# SNES_RGBAmp.net
KiCad netlist of a schematic drawn in EAGLE
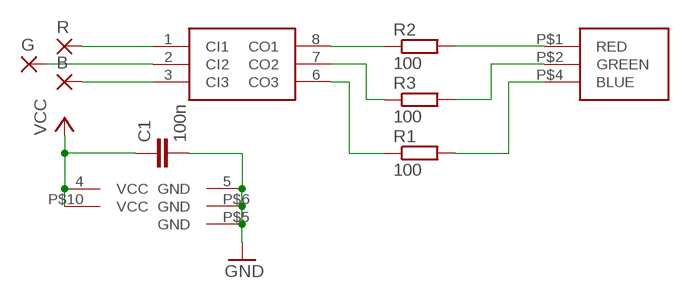
[diagram p0: schematic, sheet 1]

(export (version "E")
  (design (tool "Eeschema 10.0.6"))
  (components
    (comp (ref "B")
      (value "SMD2")
      (footprint "eagle-import:SMD1,27-2,54")
      (libsource (lib "eagle-import") (part "SMD2"))
    )
    (comp (ref "C1")
      (value "100n")
      (footprint "eagle-import:Z0805")
      (libsource (lib "eagle-import") (part "C0805"))
    )
    (comp (ref "G")
      (value "SMD2")
      (footprint "eagle-import:SMD1,27-2,54")
      (libsource (lib "eagle-import") (part "SMD2"))
    )
    (comp (ref "R")
      (value "SMD2")
      (footprint "eagle-import:SMD1,27-2,54")
      (libsource (lib "eagle-import") (part "SMD2"))
    )
    (comp (ref "R1")
      (value "100")
      (footprint "eagle-import:Z0805")
      (libsource (lib "eagle-import") (part "R0805"))
    )
    (comp (ref "R2")
      (value "100")
      (footprint "eagle-import:Z0805")
      (libsource (lib "eagle-import") (part "R0805"))
    )
    (comp (ref "R3")
      (value "100")
      (footprint "eagle-import:Z0805")
      (libsource (lib "eagle-import") (part "R0805"))
    )
    (comp (ref "U$1")
      (value "THS7314")
      (footprint "eagle-import:THS7314")
      (libsource (lib "eagle-import") (part "THS7314"))
    )
    (comp (ref "U$3")
      (value "SNES_MULTIAV_RGB_ONLY")
      (footprint "eagle-import:SNES_MULTIAV_RGB_ONLY")
      (libsource (lib "eagle-import") (part "SNES_MULTIAV_RGB_ONLY"))
    )
  )
  (nets
    (net (code "1") (name "GND") (class "Default")
      (node (ref "C1") (pin "2") (pinfunction "2_2") (pintype "passive"))
      (node (ref "U$1") (pin "5") (pinfunction "GND_5") (pintype "bidirectional"))
      (node (ref "U$3") (pin "P$5") (pinfunction "GND_P$5") (pintype "bidirectional"))
      (node (ref "U$3") (pin "P$6") (pinfunction "GND_P$6") (pintype "bidirectional"))
    )
    (net (code "2") (name "Net-(B-P)") (class "Default")
      (node (ref "B") (pin "1") (pinfunction "P_1") (pintype "passive"))
      (node (ref "U$1") (pin "3") (pinfunction "CI3_3") (pintype "bidirectional"))
    )
    (net (code "3") (name "Net-(G-P)") (class "Default")
      (node (ref "G") (pin "1") (pinfunction "P_1") (pintype "passive"))
      (node (ref "U$1") (pin "2") (pinfunction "CI2_2") (pintype "bidirectional"))
    )
    (net (code "4") (name "Net-(R-P)") (class "Default")
      (node (ref "R") (pin "1") (pinfunction "P_1") (pintype "passive"))
      (node (ref "U$1") (pin "1") (pinfunction "CI1_1") (pintype "bidirectional"))
    )
    (net (code "5") (name "Net-(U$1A-CO1)") (class "Default")
      (node (ref "R2") (pin "1") (pinfunction "1_1") (pintype "passive"))
      (node (ref "U$1") (pin "8") (pinfunction "CO1_8") (pintype "bidirectional"))
    )
    (net (code "6") (name "Net-(U$1A-CO2)") (class "Default")
      (node (ref "R3") (pin "1") (pinfunction "1_1") (pintype "passive"))
      (node (ref "U$1") (pin "7") (pinfunction "CO2_7") (pintype "bidirectional"))
    )
    (net (code "7") (name "Net-(U$1A-CO3)") (class "Default")
      (node (ref "R1") (pin "1") (pinfunction "1_1") (pintype "passive"))
      (node (ref "U$1") (pin "6") (pinfunction "CO3_6") (pintype "bidirectional"))
    )
    (net (code "8") (name "Net-(U$3C-BLUE)") (class "Default")
      (node (ref "R1") (pin "2") (pinfunction "2_2") (pintype "passive"))
      (node (ref "U$3") (pin "P$4") (pinfunction "BLUE_P$4") (pintype "bidirectional"))
    )
    (net (code "9") (name "Net-(U$3C-GREEN)") (class "Default")
      (node (ref "R3") (pin "2") (pinfunction "2_2") (pintype "passive"))
      (node (ref "U$3") (pin "P$2") (pinfunction "GREEN_P$2") (pintype "bidirectional"))
    )
    (net (code "10") (name "Net-(U$3C-RED)") (class "Default")
      (node (ref "R2") (pin "2") (pinfunction "2_2") (pintype "passive"))
      (node (ref "U$3") (pin "P$1") (pinfunction "RED_P$1") (pintype "bidirectional"))
    )
    (net (code "11") (name "VCC") (class "Default")
      (node (ref "C1") (pin "1") (pinfunction "1_1") (pintype "passive"))
      (node (ref "U$1") (pin "4") (pinfunction "VCC_4") (pintype "bidirectional"))
      (node (ref "U$3") (pin "P$10") (pinfunction "VCC_P$10") (pintype "bidirectional"))
    )
  )
)
